# 16-MT7688AN_Power-F.net
KiCad netlist of a schematic drawn in Altium Designer
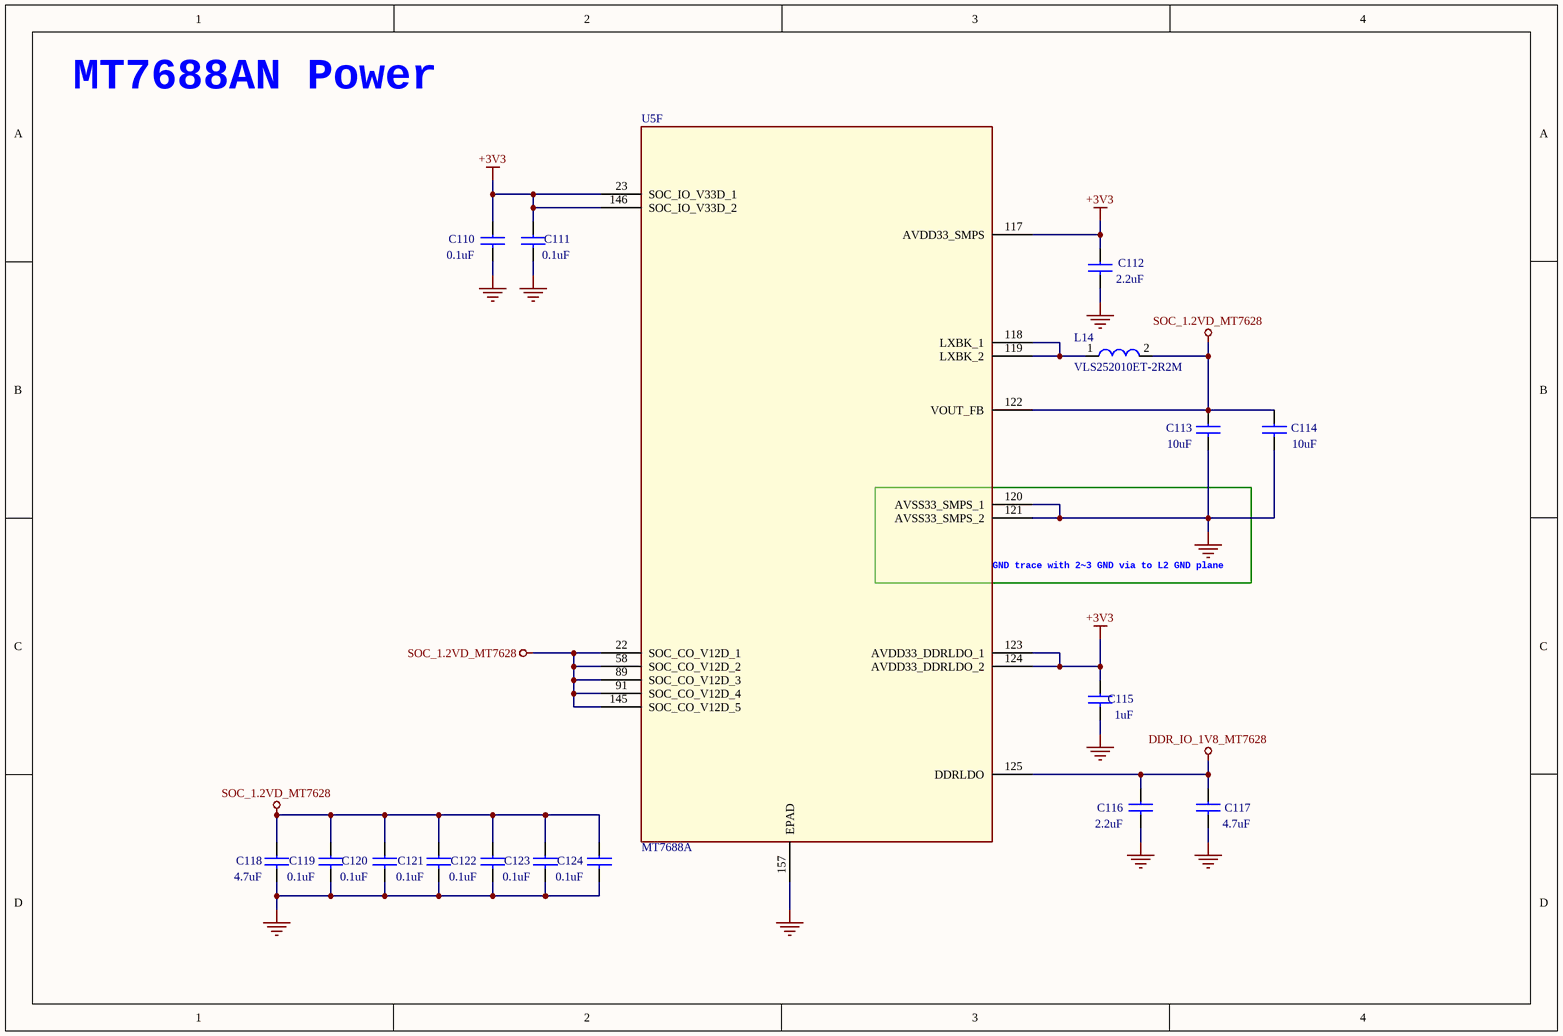
[diagram p0: 16-MT7688AN Power-F.SchDoc]

(export (version "E")
  (design (tool "Eeschema 10.0.6"))
  (components
    (comp (ref "C110")
      (value "0.1uF")
      (footprint "CAPC1005X55X25NL05T10")
      (libsource (lib "MT7688AN") (part "CAP NP"))
    )
    (comp (ref "C111")
      (value "0.1uF")
      (footprint "CAPC1005X55X25NL05T10")
      (libsource (lib "MT7688AN") (part "CAP NP"))
    )
    (comp (ref "C112")
      (value "2.2uF")
      (footprint "CAPC1608X90X35NL10T15")
      (libsource (lib "MT7688AN") (part "CAP NP"))
    )
    (comp (ref "C113")
      (value "10uF")
      (footprint "CAPC1608X90X35NL10T15")
      (libsource (lib "MT7688AN") (part "CAP NP"))
    )
    (comp (ref "C114")
      (value "10uF")
      (footprint "CAPC1608X90X35NL10T15")
      (libsource (lib "MT7688AN") (part "CAP NP"))
    )
    (comp (ref "C115")
      (value "1uF")
      (footprint "CAPC1608X90X35NL10T15")
      (libsource (lib "MT7688AN") (part "CAP NP"))
    )
    (comp (ref "C116")
      (value "2.2uF")
      (footprint "CAPC1608X90X35NL10T15")
      (libsource (lib "MT7688AN") (part "CAP NP"))
    )
    (comp (ref "C117")
      (value "4.7uF")
      (footprint "CAPC1005X55X25NL05T10")
      (libsource (lib "MT7688AN") (part "CAP NP"))
    )
    (comp (ref "C118")
      (value "4.7uF")
      (footprint "CAPC1005X55X25NL05T10")
      (libsource (lib "MT7688AN") (part "CAP NP"))
    )
    (comp (ref "C119")
      (value "0.1uF")
      (footprint "CAPC1005X55X25NL05T10")
      (libsource (lib "MT7688AN") (part "CAP NP"))
    )
    (comp (ref "C120")
      (value "0.1uF")
      (footprint "CAPC1005X55X25NL05T10")
      (libsource (lib "MT7688AN") (part "CAP NP"))
    )
    (comp (ref "C121")
      (value "0.1uF")
      (footprint "CAPC1005X55X25NL05T10")
      (libsource (lib "MT7688AN") (part "CAP NP"))
    )
    (comp (ref "C122")
      (value "0.1uF")
      (footprint "CAPC1005X55X25NL05T10")
      (libsource (lib "MT7688AN") (part "CAP NP"))
    )
    (comp (ref "C123")
      (value "0.1uF")
      (footprint "CAPC1005X55X25NL05T10")
      (libsource (lib "MT7688AN") (part "CAP NP"))
    )
    (comp (ref "C124")
      (value "0.1uF")
      (footprint "CAPC1005X55X25NL05T10")
      (libsource (lib "MT7688AN") (part "CAP NP"))
    )
    (comp (ref "L14")
      (value "VLS252010ET-2R2M")
      (footprint "VLS252010/TDK INDUCTOR")
      (description "IND 0805 METAL 2.2uH 0.19R 1.2A T=1.0mm")
      (libsource (lib "MT7688AN") (part "L/0402"))
    )
    (comp (ref "U5")
      (value "MT7688A")
      (footprint "MT7628AN$2F$DRQFN156$2F$SMD$2F$P0.5$2F$12X12")
      (libsource (lib "MT7688AN") (part "MT7620N-n_26"))
    )
  )
  (nets
    (net (code "1") (name "+3V3") (class "Default")
      (node (ref "C110") (pin "1") (pinfunction "1_1") (pintype "passive"))
      (node (ref "C111") (pin "1") (pinfunction "1_1") (pintype "passive"))
      (node (ref "C112") (pin "1") (pinfunction "1_1") (pintype "passive"))
      (node (ref "C115") (pin "1") (pinfunction "1_1") (pintype "passive"))
      (node (ref "U5") (pin "117") (pinfunction "AVDD33_SMPS_117") (pintype "power_in"))
      (node (ref "U5") (pin "123") (pinfunction "AVDD33_DDRLDO_1_123") (pintype "power_in"))
      (node (ref "U5") (pin "124") (pinfunction "AVDD33_DDRLDO_2_124") (pintype "power_in"))
      (node (ref "U5") (pin "146") (pinfunction "SOC_IO_V33D_2_146") (pintype "power_in"))
      (node (ref "U5") (pin "23") (pinfunction "SOC_IO_V33D_1_23") (pintype "power_in"))
    )
    (net (code "2") (name "DDR_IO_1V8_MT7628") (class "Default")
      (node (ref "C116") (pin "1") (pinfunction "1_1") (pintype "passive"))
      (node (ref "C117") (pin "1") (pinfunction "1_1") (pintype "passive"))
      (node (ref "U5") (pin "125") (pinfunction "DDRLDO_125") (pintype "power_in"))
    )
    (net (code "3") (name "GND") (class "Default")
      (node (ref "C110") (pin "2") (pinfunction "2_2") (pintype "passive"))
      (node (ref "C111") (pin "2") (pinfunction "2_2") (pintype "passive"))
      (node (ref "C112") (pin "2") (pinfunction "2_2") (pintype "passive"))
      (node (ref "C113") (pin "2") (pinfunction "2_2") (pintype "passive"))
      (node (ref "C114") (pin "2") (pinfunction "2_2") (pintype "passive"))
      (node (ref "C115") (pin "2") (pinfunction "2_2") (pintype "passive"))
      (node (ref "C116") (pin "2") (pinfunction "2_2") (pintype "passive"))
      (node (ref "C117") (pin "2") (pinfunction "2_2") (pintype "passive"))
      (node (ref "C118") (pin "2") (pinfunction "2_2") (pintype "passive"))
      (node (ref "C119") (pin "2") (pinfunction "2_2") (pintype "passive"))
      (node (ref "C120") (pin "2") (pinfunction "2_2") (pintype "passive"))
      (node (ref "C121") (pin "2") (pinfunction "2_2") (pintype "passive"))
      (node (ref "C122") (pin "2") (pinfunction "2_2") (pintype "passive"))
      (node (ref "C123") (pin "2") (pinfunction "2_2") (pintype "passive"))
      (node (ref "C124") (pin "2") (pinfunction "2_2") (pintype "passive"))
      (node (ref "U5") (pin "120") (pinfunction "AVSS33_SMPS_1_120") (pintype "power_in"))
      (node (ref "U5") (pin "121") (pinfunction "AVSS33_SMPS_2_121") (pintype "power_in"))
      (node (ref "U5") (pin "157") (pinfunction "EPAD_157") (pintype "power_in"))
    )
    (net (code "4") (name "Net-(U5F-LXBK_1)") (class "Default")
      (node (ref "L14") (pin "1") (pinfunction "1_1") (pintype "passive"))
      (node (ref "U5") (pin "118") (pinfunction "LXBK_1_118") (pintype "passive"))
      (node (ref "U5") (pin "119") (pinfunction "LXBK_2_119") (pintype "passive"))
    )
    (net (code "5") (name "SOC_1.2VD_MT7628") (class "Default")
      (node (ref "C113") (pin "1") (pinfunction "1_1") (pintype "passive"))
      (node (ref "C114") (pin "1") (pinfunction "1_1") (pintype "passive"))
      (node (ref "C118") (pin "1") (pinfunction "1_1") (pintype "passive"))
      (node (ref "C119") (pin "1") (pinfunction "1_1") (pintype "passive"))
      (node (ref "C120") (pin "1") (pinfunction "1_1") (pintype "passive"))
      (node (ref "C121") (pin "1") (pinfunction "1_1") (pintype "passive"))
      (node (ref "C122") (pin "1") (pinfunction "1_1") (pintype "passive"))
      (node (ref "C123") (pin "1") (pinfunction "1_1") (pintype "passive"))
      (node (ref "C124") (pin "1") (pinfunction "1_1") (pintype "passive"))
      (node (ref "L14") (pin "2") (pinfunction "2_2") (pintype "passive"))
      (node (ref "U5") (pin "122") (pinfunction "VOUT_FB_122") (pintype "power_in"))
      (node (ref "U5") (pin "145") (pinfunction "SOC_CO_V12D_5_145") (pintype "power_in"))
      (node (ref "U5") (pin "22") (pinfunction "SOC_CO_V12D_1_22") (pintype "power_in"))
      (node (ref "U5") (pin "58") (pinfunction "SOC_CO_V12D_2_58") (pintype "power_in"))
      (node (ref "U5") (pin "89") (pinfunction "SOC_CO_V12D_3_89") (pintype "power_in"))
      (node (ref "U5") (pin "91") (pinfunction "SOC_CO_V12D_4_91") (pintype "power_in"))
    )
  )
)
